# GB-classic-Link-connector-debug.net
KiCad netlist of a schematic drawn in EAGLE
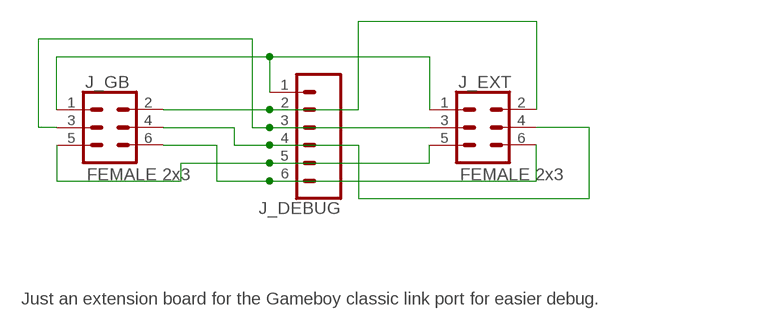
[diagram p0: schematic, sheet 1]

(export (version "E")
  (design (tool "Eeschema 10.0.6"))
  (components
    (comp (ref "J_DEBUG")
      (value "CONN_06LONGPADS")
      (footprint "eagle-import:1X06_LONGPADS")
      (libsource (lib "eagle-import") (part "CONN_06LONGPADS"))
    )
    (comp (ref "J_EXT")
      (value "FEMALE 2x3")
      (footprint "eagle-import:2X3")
      (libsource (lib "eagle-import") (part "CONN_03X2FEMALE"))
    )
    (comp (ref "J_GB")
      (value "FEMALE 2x3")
      (footprint "eagle-import:2X3")
      (libsource (lib "eagle-import") (part "CONN_03X2FEMALE"))
    )
  )
  (nets
    (net (code "1") (name "Net-(J_DEBUG-Pad1)") (class "Default")
      (node (ref "J_DEBUG") (pin "1") (pinfunction "1_1") (pintype "passive"))
      (node (ref "J_EXT") (pin "1") (pinfunction "1_1") (pintype "bidirectional"))
      (node (ref "J_GB") (pin "1") (pinfunction "1_1") (pintype "bidirectional"))
    )
    (net (code "2") (name "Net-(J_DEBUG-Pad2)") (class "Default")
      (node (ref "J_DEBUG") (pin "2") (pinfunction "2_2") (pintype "passive"))
      (node (ref "J_EXT") (pin "2") (pinfunction "2_2") (pintype "bidirectional"))
      (node (ref "J_GB") (pin "2") (pinfunction "2_2") (pintype "bidirectional"))
    )
    (net (code "3") (name "Net-(J_DEBUG-Pad3)") (class "Default")
      (node (ref "J_DEBUG") (pin "3") (pinfunction "3_3") (pintype "passive"))
      (node (ref "J_EXT") (pin "3") (pinfunction "3_3") (pintype "bidirectional"))
      (node (ref "J_GB") (pin "3") (pinfunction "3_3") (pintype "bidirectional"))
    )
    (net (code "4") (name "Net-(J_DEBUG-Pad4)") (class "Default")
      (node (ref "J_DEBUG") (pin "4") (pinfunction "4_4") (pintype "passive"))
      (node (ref "J_EXT") (pin "4") (pinfunction "4_4") (pintype "bidirectional"))
      (node (ref "J_GB") (pin "4") (pinfunction "4_4") (pintype "bidirectional"))
    )
    (net (code "5") (name "Net-(J_DEBUG-Pad5)") (class "Default")
      (node (ref "J_DEBUG") (pin "5") (pinfunction "5_5") (pintype "passive"))
      (node (ref "J_EXT") (pin "5") (pinfunction "5_5") (pintype "bidirectional"))
      (node (ref "J_GB") (pin "5") (pinfunction "5_5") (pintype "bidirectional"))
    )
    (net (code "6") (name "Net-(J_DEBUG-Pad6)") (class "Default")
      (node (ref "J_DEBUG") (pin "6") (pinfunction "6_6") (pintype "passive"))
      (node (ref "J_EXT") (pin "6") (pinfunction "6_6") (pintype "bidirectional"))
      (node (ref "J_GB") (pin "6") (pinfunction "6_6") (pintype "bidirectional"))
    )
  )
)
